# Driver_Push_Pull.net
KiCad netlist of a schematic drawn in Altium Designer
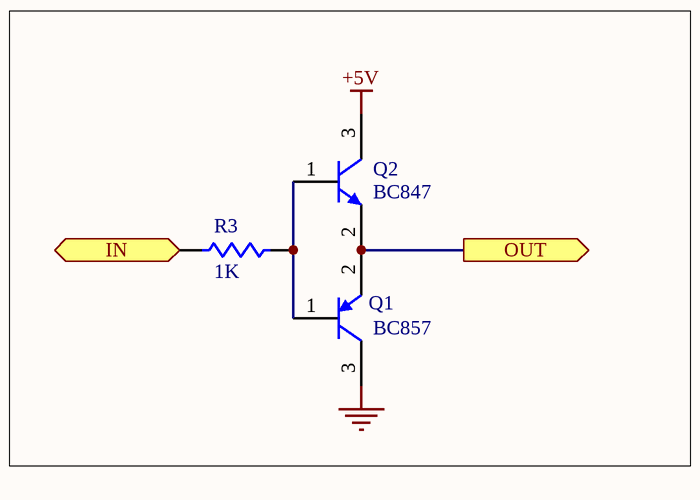
[diagram p0: Driver_Push Pull.SchDoc]

(export (version "E")
  (design (tool "Eeschema 10.0.6"))
  (components
    (comp (ref "Q1")
      (value "BC857")
      (footprint "SOT23-3N")
      (description "Silicon Bipolar Transistor")
      (libsource (lib "my Libraries") (part "BC857"))
    )
    (comp (ref "Q2")
      (value "BC847")
      (footprint "SOT23-3N")
      (description "Silicon Bipolar Transistor")
      (libsource (lib "my Libraries") (part "BC847"))
    )
    (comp (ref "R3")
      (value "1K")
      (footprint "0805")
      (description "Resistor")
      (fields (field (name "MANUFACTURER") "Generic Components") (field (name "PUBLISHER") "Altium Limited"))
      (libsource (lib "Miscellaneous Devices") (part "Res1"))
    )
  )
  (nets
    (net (code "1") (name "+5V") (class "Default")
      (node (ref "Q2") (pin "3") (pinfunction "C_3") (pintype "passive"))
    )
    (net (code "2") (name "/IN") (class "Default")
      (node (ref "R3") (pin "2") (pinfunction "2_2") (pintype "passive"))
    )
    (net (code "3") (name "/OUT") (class "Default")
      (node (ref "Q1") (pin "2") (pinfunction "E_2") (pintype "passive"))
      (node (ref "Q2") (pin "2") (pinfunction "E_2") (pintype "passive"))
    )
    (net (code "4") (name "GND") (class "Default")
      (node (ref "Q1") (pin "3") (pinfunction "C_3") (pintype "passive"))
    )
    (net (code "5") (name "Net-(Q1-B)") (class "Default")
      (node (ref "Q1") (pin "1") (pinfunction "B_1") (pintype "passive"))
      (node (ref "Q2") (pin "1") (pinfunction "B_1") (pintype "passive"))
      (node (ref "R3") (pin "1") (pinfunction "1_1") (pintype "passive"))
    )
  )
)
